# Comms.net
KiCad netlist of a schematic drawn in Altium Designer
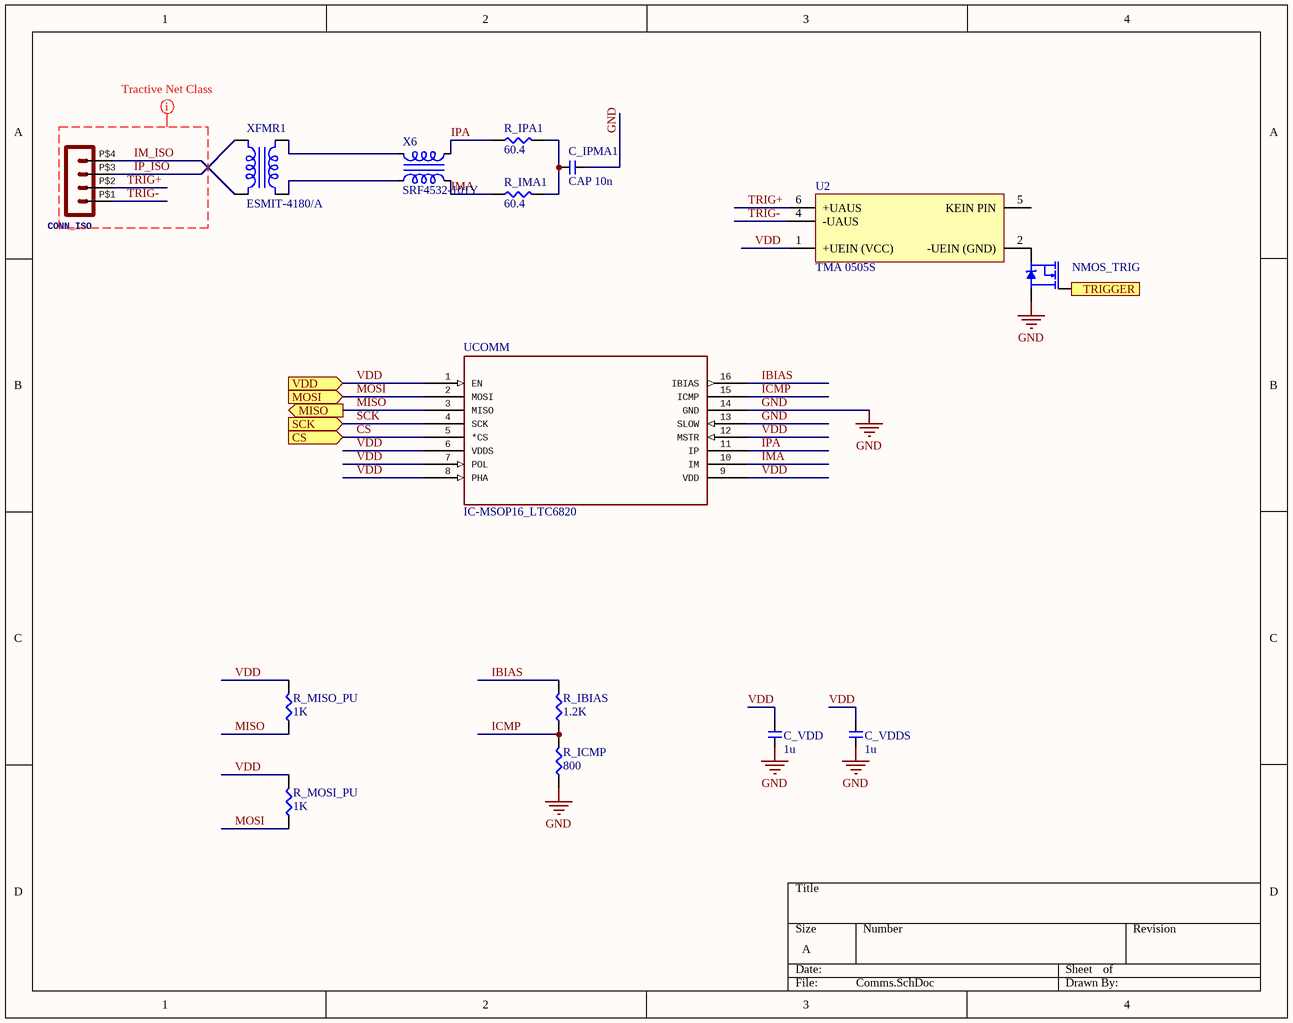
[diagram p0: Comms.SchDoc]

(export (version "E")
  (design (tool "Eeschema 10.0.6"))
  (components
    (comp (ref "CONN_ISO")
      (value "Molex - Micro-Fit 3.0 Series connector,  3.00mm (0.118\") pitch header, 4 positions.")
      (footprint "43650-0424")
      (libsource (lib "ife19_Elec_Conn_Library") (part "POS4_MF43650-0424"))
    )
    (comp (ref "C_IPMA1")
      (value "CAP 10n")
      (footprint "CAP-0603")
      (description "CAP-0603")
      (libsource (lib "ife18_TS_BMS_LTC6813_v2_Library") (part "CAP-0603"))
    )
    (comp (ref "C_VDD")
      (value "1u")
      (footprint "CAP-0603")
      (libsource (lib "altium-import") (part "root_1_CAP-0603_"))
    )
    (comp (ref "C_VDDS")
      (value "1u")
      (footprint "CAP-0603")
      (libsource (lib "altium-import") (part "root_1_CAP-0603_"))
    )
    (comp (ref "NMOS_TRIG")
      (value "NMOS-SOT23")
      (footprint "SOT23")
      (libsource (lib "altium-import") (part "root_0_NMOS-SOT23_"))
    )
    (comp (ref "R_IBIAS")
      (value "1.2K")
      (footprint "RES-0603")
      (libsource (lib "altium-import") (part "root_1_RES-0603_"))
    )
    (comp (ref "R_ICMP")
      (value "800")
      (footprint "RES-0603")
      (libsource (lib "altium-import") (part "root_1_RES-0603_"))
    )
    (comp (ref "R_IMA1")
      (value "60.4")
      (footprint "RES-0603")
      (libsource (lib "ife18_TS_BMS_LTC6813_v2_Library") (part "RES-0603"))
    )
    (comp (ref "R_IPA1")
      (value "60.4")
      (footprint "RES-0603")
      (libsource (lib "ife18_TS_BMS_LTC6813_v2_Library") (part "RES-0603"))
    )
    (comp (ref "R_MISO_PU")
      (value "1K")
      (footprint "RES-0603")
      (libsource (lib "altium-import") (part "root_1_RES-0603_"))
    )
    (comp (ref "R_MOSI_PU")
      (value "1K")
      (footprint "RES-0603")
      (libsource (lib "altium-import") (part "root_1_RES-0603_"))
    )
    (comp (ref "U2")
      (value "TMA 0505S")
      (footprint "TRACO-TMA0505S")
      (description "DC/DC Converter, 200 mA, 5 VDC, -40 to 85 degC, 5-Pin THD, RoHS")
      (fields (field (name "MANUFACTURER") "Tracopower"))
      (libsource (lib "Altium Content Vault") (part "TRACO-TMA0505S-5"))
    )
    (comp (ref "UCOMM")
      (value "IC-MSOP16_LTC6820")
      (footprint "MSOP16")
      (libsource (lib "altium-import") (part "root_0_IC-MSOP16_LTC6820_"))
    )
    (comp (ref "X6")
      (value "SRF4532-101Y")
      (footprint "SRF4532")
      (libsource (lib "ife19_Elec_Library") (part "CMC_SRF4532"))
    )
    (comp (ref "XFMR1")
      (value "ESMIT-4180/A")
      (footprint "ISOXFMR_ESMIT4180")
      (libsource (lib "ife19_Elec_Library") (part "ISOXFMR_ESMIT4180"))
    )
  )
  (nets
    (net (code "1") (name "/CS") (class "Default")
      (node (ref "UCOMM") (pin "5") (pinfunction "*CS_5") (pintype "passive"))
    )
    (net (code "2") (name "/IBIAS") (class "Default")
      (node (ref "R_IBIAS") (pin "2") (pinfunction "2_2") (pintype "passive"))
      (node (ref "UCOMM") (pin "16") (pinfunction "IBIAS_16") (pintype "output"))
    )
    (net (code "3") (name "/ICMP") (class "Default")
      (node (ref "R_IBIAS") (pin "1") (pinfunction "1_1") (pintype "passive"))
      (node (ref "R_ICMP") (pin "2") (pinfunction "2_2") (pintype "passive"))
      (node (ref "UCOMM") (pin "15") (pinfunction "ICMP_15") (pintype "passive"))
    )
    (net (code "4") (name "/IMA") (class "Default")
      (node (ref "R_IMA1") (pin "2") (pinfunction "2_2") (pintype "passive"))
      (node (ref "UCOMM") (pin "10") (pinfunction "IM_10") (pintype "passive"))
      (node (ref "X6") (pin "1") (pinfunction "1_1") (pintype "passive"))
    )
    (net (code "5") (name "/IM_ISO") (class "Default")
      (node (ref "CONN_ISO") (pin "P$4") (pinfunction "4_P$4") (pintype "passive"))
      (node (ref "XFMR1") (pin "1") (pinfunction "1_1") (pintype "passive"))
    )
    (net (code "6") (name "/IPA") (class "Default")
      (node (ref "R_IPA1") (pin "2") (pinfunction "2_2") (pintype "passive"))
      (node (ref "UCOMM") (pin "11") (pinfunction "IP_11") (pintype "passive"))
      (node (ref "X6") (pin "4") (pinfunction "4_4") (pintype "passive"))
    )
    (net (code "7") (name "/IP_ISO") (class "Default")
      (node (ref "CONN_ISO") (pin "P$3") (pinfunction "3_P$3") (pintype "passive"))
      (node (ref "XFMR1") (pin "2") (pinfunction "2_2") (pintype "passive"))
    )
    (net (code "8") (name "/MISO") (class "Default")
      (node (ref "R_MISO_PU") (pin "1") (pinfunction "1_1") (pintype "passive"))
      (node (ref "UCOMM") (pin "3") (pinfunction "MISO_3") (pintype "passive"))
    )
    (net (code "9") (name "/MOSI") (class "Default")
      (node (ref "R_MOSI_PU") (pin "1") (pinfunction "1_1") (pintype "passive"))
      (node (ref "UCOMM") (pin "2") (pinfunction "MOSI_2") (pintype "passive"))
    )
    (net (code "10") (name "/SCK") (class "Default")
      (node (ref "UCOMM") (pin "4") (pinfunction "SCK_4") (pintype "passive"))
    )
    (net (code "11") (name "/TRIG+") (class "Default")
      (node (ref "CONN_ISO") (pin "P$2") (pinfunction "2_P$2") (pintype "passive"))
      (node (ref "U2") (pin "6") (pinfunction "+UAUS_6") (pintype "passive"))
    )
    (net (code "12") (name "/TRIG-") (class "Default")
      (node (ref "CONN_ISO") (pin "P$1") (pinfunction "1_P$1") (pintype "passive"))
      (node (ref "U2") (pin "4") (pinfunction "-UAUS_4") (pintype "passive"))
    )
    (net (code "13") (name "/TRIGGER") (class "Default")
      (node (ref "NMOS_TRIG") (pin "1") (pinfunction "G_1") (pintype "passive"))
    )
    (net (code "14") (name "/VDD") (class "Default")
      (node (ref "C_VDD") (pin "2") (pinfunction "2_2") (pintype "passive"))
      (node (ref "C_VDDS") (pin "2") (pinfunction "2_2") (pintype "passive"))
      (node (ref "R_MISO_PU") (pin "2") (pinfunction "2_2") (pintype "passive"))
      (node (ref "R_MOSI_PU") (pin "2") (pinfunction "2_2") (pintype "passive"))
      (node (ref "U2") (pin "1") (pinfunction "+UEIN_(VCC)_1") (pintype "power_in"))
      (node (ref "UCOMM") (pin "1") (pinfunction "EN_1") (pintype "input"))
      (node (ref "UCOMM") (pin "12") (pinfunction "MSTR_12") (pintype "input"))
      (node (ref "UCOMM") (pin "6") (pinfunction "VDDS_6") (pintype "power_in"))
      (node (ref "UCOMM") (pin "7") (pinfunction "POL_7") (pintype "input"))
      (node (ref "UCOMM") (pin "8") (pinfunction "PHA_8") (pintype "input"))
      (node (ref "UCOMM") (pin "9") (pinfunction "VDD_9") (pintype "power_in"))
    )
    (net (code "15") (name "GND") (class "Default")
      (node (ref "C_IPMA1") (pin "1") (pinfunction "1_1") (pintype "passive"))
      (node (ref "C_VDD") (pin "1") (pinfunction "1_1") (pintype "passive"))
      (node (ref "C_VDDS") (pin "1") (pinfunction "1_1") (pintype "passive"))
      (node (ref "NMOS_TRIG") (pin "2") (pinfunction "S_2") (pintype "passive"))
      (node (ref "R_ICMP") (pin "1") (pinfunction "1_1") (pintype "passive"))
      (node (ref "UCOMM") (pin "13") (pinfunction "SLOW_13") (pintype "input"))
      (node (ref "UCOMM") (pin "14") (pinfunction "GND_14") (pintype "power_in"))
    )
    (net (code "16") (name "Net-(C_IPMA1-Pad2)") (class "Default")
      (node (ref "C_IPMA1") (pin "2") (pinfunction "2_2") (pintype "passive"))
      (node (ref "R_IMA1") (pin "1") (pinfunction "1_1") (pintype "passive"))
      (node (ref "R_IPA1") (pin "1") (pinfunction "1_1") (pintype "passive"))
    )
    (net (code "17") (name "Net-(NMOS_TRIG-D)") (class "Default")
      (node (ref "NMOS_TRIG") (pin "3") (pinfunction "D_3") (pintype "passive"))
      (node (ref "U2") (pin "2") (pinfunction "-UEIN_(GND)_2") (pintype "power_in"))
    )
    (net (code "18") (name "Net-(X6-Pad2)") (class "Default")
      (node (ref "X6") (pin "2") (pinfunction "2_2") (pintype "passive"))
      (node (ref "XFMR1") (pin "4") (pinfunction "4_4") (pintype "passive"))
    )
    (net (code "19") (name "Net-(X6-Pad3)") (class "Default")
      (node (ref "X6") (pin "3") (pinfunction "3_3") (pintype "passive"))
      (node (ref "XFMR1") (pin "3") (pinfunction "3_3") (pintype "passive"))
    )
    (net (code "20") (name "unconnected-(U2-KEIN_PIN-Pad5)") (class "Default")
      (node (ref "U2") (pin "5") (pinfunction "KEIN_PIN_5") (pintype "passive"))
    )
  )
)
